# ESP32headerboard.net
KiCad netlist of a schematic drawn in Altium Designer
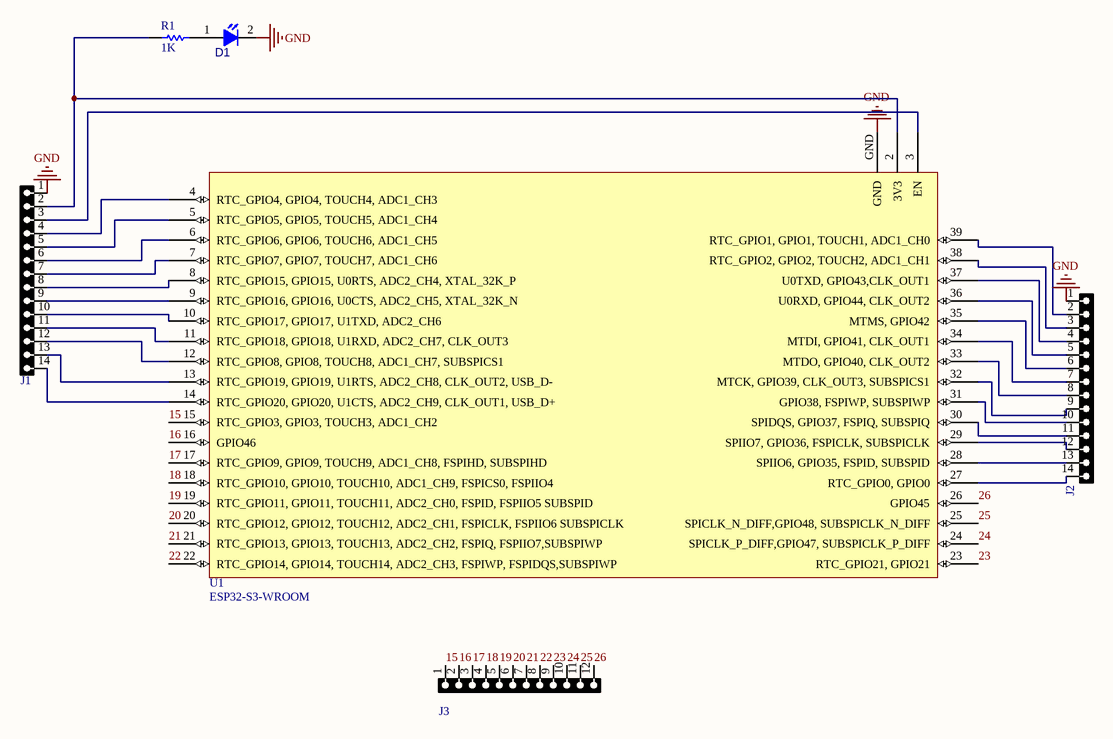
[diagram p0: ESP32headerboard.SchDoc]

(export (version "E")
  (design (tool "Eeschema 10.0.6"))
  (components
    (comp (ref "D1")
      (value "LED SMD 1206")
      (footprint "LED SMD 1206 (Blue)")
      (fields (field (name "DESIGNED BY:") "MJKhodami"))
      (libsource (lib "Devices_OMIDF") (part "LED SMD 1206"))
    )
    (comp (ref "J1")
      (value "HDRF14")
      (footprint "HDR 1X14")
      (description "CONN, HEADER, Female, pitch: 2.54mm, 14POS")
      (fields (field (name "DESIGNED BY:") "MJKhodami"))
      (libsource (lib "Devices_OMIDF") (part "HDR_1X14"))
    )
    (comp (ref "J2")
      (value "HDRF14")
      (footprint "HDR 1X14")
      (description "CONN, HEADER, Female, pitch: 2.54mm, 14POS")
      (fields (field (name "DESIGNED BY:") "MJKhodami"))
      (libsource (lib "Devices_OMIDF") (part "HDR_1X14"))
    )
    (comp (ref "J3")
      (value "HDRF12")
      (footprint "HDR 1X12")
      (description "CONN, HEADER, Female, pitch: 2.54mm, 12POS")
      (fields (field (name "DESIGNED BY:") "MJKhodami"))
      (libsource (lib "Devices_OMIDF") (part "HDR_1X12"))
    )
    (comp (ref "R1")
      (value "1K")
      (footprint "SMD-1206-RES")
      (description "Resistor SMD 1206")
      (fields (field (name "DESIGNED BY:") "MJKhodami"))
      (libsource (lib "Devices_OMIDF") (part "Resistor SMD 1206"))
    )
    (comp (ref "U1")
      (value "ESP32-S3-WROOM")
      (footprint "ESP32-S3-WROOM-1U-N8R8")
      (fields (field (name "DESIGNED BY:") "MJKhodami"))
      (libsource (lib "Devices_OMIDF") (part "ESP32-S3-WROOM-1U-N8R8"))
    )
  )
  (nets
    (net (code "1") (name "/15") (class "Default")
      (node (ref "J3") (pin "1") (pinfunction "1_1") (pintype "passive"))
      (node (ref "U1") (pin "15") (pinfunction "RTC_GPIO3,_GPIO3,_TOUCH3,_ADC1_CH2_15") (pintype "bidirectional"))
    )
    (net (code "2") (name "/16") (class "Default")
      (node (ref "J3") (pin "2") (pinfunction "2_2") (pintype "passive"))
      (node (ref "U1") (pin "16") (pinfunction "GPIO46_16") (pintype "bidirectional"))
    )
    (net (code "3") (name "/17") (class "Default")
      (node (ref "J3") (pin "3") (pinfunction "3_3") (pintype "passive"))
      (node (ref "U1") (pin "17") (pinfunction "RTC_GPIO9,_GPIO9,_TOUCH9,_ADC1_CH8,_FSPIHD,_SUBSPIHD_17") (pintype "bidirectional"))
    )
    (net (code "4") (name "/18") (class "Default")
      (node (ref "J3") (pin "4") (pinfunction "4_4") (pintype "passive"))
      (node (ref "U1") (pin "18") (pinfunction "RTC_GPIO10,_GPIO10,_TOUCH10,_ADC1_CH9,_FSPICS0,_FSPIIO4_18") (pintype "bidirectional"))
    )
    (net (code "5") (name "/19") (class "Default")
      (node (ref "J3") (pin "5") (pinfunction "5_5") (pintype "passive"))
      (node (ref "U1") (pin "19") (pinfunction "RTC_GPIO11,_GPIO11,_TOUCH11,_ADC2_CH0,_FSPID,_FSPIIO5_SUBSPID_19") (pintype "bidirectional"))
    )
    (net (code "6") (name "/20") (class "Default")
      (node (ref "J3") (pin "6") (pinfunction "6_6") (pintype "passive"))
      (node (ref "U1") (pin "20") (pinfunction "RTC_GPIO12,_GPIO12,_TOUCH12,_ADC2_CH1,_FSPICLK,_FSPIIO6_SUBSPICLK_20") (pintype "bidirectional"))
    )
    (net (code "7") (name "/21") (class "Default")
      (node (ref "J3") (pin "7") (pinfunction "7_7") (pintype "passive"))
      (node (ref "U1") (pin "21") (pinfunction "RTC_GPIO13,_GPIO13,_TOUCH13,_ADC2_CH2,_FSPIQ,_FSPIIO7,SUBSPIWP_21") (pintype "bidirectional"))
    )
    (net (code "8") (name "/22") (class "Default")
      (node (ref "J3") (pin "8") (pinfunction "8_8") (pintype "passive"))
      (node (ref "U1") (pin "22") (pinfunction "RTC_GPIO14,_GPIO14,_TOUCH14,_ADC2_CH3,_FSPIWP,_FSPIDQS,SUBSPIWP_22") (pintype "bidirectional"))
    )
    (net (code "9") (name "/23") (class "Default")
      (node (ref "J3") (pin "9") (pinfunction "9_9") (pintype "passive"))
      (node (ref "U1") (pin "23") (pinfunction "RTC_GPIO21,_GPIO21_23") (pintype "bidirectional"))
    )
    (net (code "10") (name "/24") (class "Default")
      (node (ref "J3") (pin "10") (pinfunction "10_10") (pintype "passive"))
      (node (ref "U1") (pin "24") (pinfunction "SPICLK_P_DIFF,GPIO47,_SUBSPICLK_P_DIFF_24") (pintype "bidirectional"))
    )
    (net (code "11") (name "/25") (class "Default")
      (node (ref "J3") (pin "11") (pinfunction "11_11") (pintype "passive"))
      (node (ref "U1") (pin "25") (pinfunction "SPICLK_N_DIFF,GPIO48,_SUBSPICLK_N_DIFF_25") (pintype "bidirectional"))
    )
    (net (code "12") (name "/26") (class "Default")
      (node (ref "J3") (pin "12") (pinfunction "12_12") (pintype "passive"))
      (node (ref "U1") (pin "26") (pinfunction "GPIO45_26") (pintype "bidirectional"))
    )
    (net (code "13") (name "GND") (class "Default")
      (node (ref "D1") (pin "2") (pinfunction "CATHODE_2") (pintype "passive"))
      (node (ref "J1") (pin "1") (pinfunction "1_1") (pintype "passive"))
      (node (ref "J2") (pin "1") (pinfunction "1_1") (pintype "passive"))
      (node (ref "U1") (pin "GND") (pinfunction "GND_GND") (pintype "passive"))
    )
    (net (code "14") (name "Net-(D1-ANODE)") (class "Default")
      (node (ref "D1") (pin "1") (pinfunction "ANODE_1") (pintype "passive"))
      (node (ref "R1") (pin "2") (pinfunction "2_2") (pintype "passive"))
    )
    (net (code "15") (name "Net-(U1-3V3)") (class "Default")
      (node (ref "J1") (pin "2") (pinfunction "2_2") (pintype "passive"))
      (node (ref "R1") (pin "1") (pinfunction "1_1") (pintype "passive"))
      (node (ref "U1") (pin "2") (pinfunction "3V3_2") (pintype "power_in"))
    )
    (net (code "16") (name "Net-(U1-EN)") (class "Default")
      (node (ref "J1") (pin "3") (pinfunction "3_3") (pintype "passive"))
      (node (ref "U1") (pin "3") (pinfunction "EN_3") (pintype "power_in"))
    )
    (net (code "17") (name "Net-(U1-GPIO38,_FSPIWP,_SUBSPIWP)") (class "Default")
      (node (ref "J2") (pin "10") (pinfunction "10_10") (pintype "passive"))
      (node (ref "U1") (pin "31") (pinfunction "GPIO38,_FSPIWP,_SUBSPIWP_31") (pintype "bidirectional"))
    )
    (net (code "18") (name "Net-(U1-MTCK,_GPIO39,_CLK_OUT3,_SUBSPICS1)") (class "Default")
      (node (ref "J2") (pin "9") (pinfunction "9_9") (pintype "passive"))
      (node (ref "U1") (pin "32") (pinfunction "MTCK,_GPIO39,_CLK_OUT3,_SUBSPICS1_32") (pintype "bidirectional"))
    )
    (net (code "19") (name "Net-(U1-MTDI,_GPIO41,_CLK_OUT1)") (class "Default")
      (node (ref "J2") (pin "7") (pinfunction "7_7") (pintype "passive"))
      (node (ref "U1") (pin "34") (pinfunction "MTDI,_GPIO41,_CLK_OUT1_34") (pintype "bidirectional"))
    )
    (net (code "20") (name "Net-(U1-MTDO,_GPIO40,_CLK_OUT2)") (class "Default")
      (node (ref "J2") (pin "8") (pinfunction "8_8") (pintype "passive"))
      (node (ref "U1") (pin "33") (pinfunction "MTDO,_GPIO40,_CLK_OUT2_33") (pintype "bidirectional"))
    )
    (net (code "21") (name "Net-(U1-MTMS,_GPIO42)") (class "Default")
      (node (ref "J2") (pin "6") (pinfunction "6_6") (pintype "passive"))
      (node (ref "U1") (pin "35") (pinfunction "MTMS,_GPIO42_35") (pintype "bidirectional"))
    )
    (net (code "22") (name "Net-(U1-RTC_GPIO0,_GPIO0)") (class "Default")
      (node (ref "J2") (pin "14") (pinfunction "14_14") (pintype "passive"))
      (node (ref "U1") (pin "27") (pinfunction "RTC_GPIO0,_GPIO0_27") (pintype "bidirectional"))
    )
    (net (code "23") (name "Net-(U1-RTC_GPIO1,_GPIO1,_TOUCH1,_ADC1_CH0)") (class "Default")
      (node (ref "J2") (pin "2") (pinfunction "2_2") (pintype "passive"))
      (node (ref "U1") (pin "39") (pinfunction "RTC_GPIO1,_GPIO1,_TOUCH1,_ADC1_CH0_39") (pintype "bidirectional"))
    )
    (net (code "24") (name "Net-(U1-RTC_GPIO2,_GPIO2,_TOUCH2,_ADC1_CH1)") (class "Default")
      (node (ref "J2") (pin "3") (pinfunction "3_3") (pintype "passive"))
      (node (ref "U1") (pin "38") (pinfunction "RTC_GPIO2,_GPIO2,_TOUCH2,_ADC1_CH1_38") (pintype "bidirectional"))
    )
    (net (code "25") (name "Net-(U1-RTC_GPIO4,_GPIO4,_TOUCH4,_ADC1_CH3)") (class "Default")
      (node (ref "J1") (pin "4") (pinfunction "4_4") (pintype "passive"))
      (node (ref "U1") (pin "4") (pinfunction "RTC_GPIO4,_GPIO4,_TOUCH4,_ADC1_CH3_4") (pintype "bidirectional"))
    )
    (net (code "26") (name "Net-(U1-RTC_GPIO5,_GPIO5,_TOUCH5,_ADC1_CH4)") (class "Default")
      (node (ref "J1") (pin "5") (pinfunction "5_5") (pintype "passive"))
      (node (ref "U1") (pin "5") (pinfunction "RTC_GPIO5,_GPIO5,_TOUCH5,_ADC1_CH4_5") (pintype "bidirectional"))
    )
    (net (code "27") (name "Net-(U1-RTC_GPIO6,_GPIO6,_TOUCH6,_ADC1_CH5)") (class "Default")
      (node (ref "J1") (pin "6") (pinfunction "6_6") (pintype "passive"))
      (node (ref "U1") (pin "6") (pinfunction "RTC_GPIO6,_GPIO6,_TOUCH6,_ADC1_CH5_6") (pintype "bidirectional"))
    )
    (net (code "28") (name "Net-(U1-RTC_GPIO7,_GPIO7,_TOUCH7,_ADC1_CH6)") (class "Default")
      (node (ref "J1") (pin "7") (pinfunction "7_7") (pintype "passive"))
      (node (ref "U1") (pin "7") (pinfunction "RTC_GPIO7,_GPIO7,_TOUCH7,_ADC1_CH6_7") (pintype "bidirectional"))
    )
    (net (code "29") (name "Net-(U1-RTC_GPIO8,_GPIO8,_TOUCH8,_ADC1_CH7,_SUBSPICS1)") (class "Default")
      (node (ref "J1") (pin "12") (pinfunction "12_12") (pintype "passive"))
      (node (ref "U1") (pin "12") (pinfunction "RTC_GPIO8,_GPIO8,_TOUCH8,_ADC1_CH7,_SUBSPICS1_12") (pintype "bidirectional"))
    )
    (net (code "30") (name "Net-(U1-RTC_GPIO15,_GPIO15,_U0RTS,_ADC2_CH4,_XTAL_32K_P)") (class "Default")
      (node (ref "J1") (pin "8") (pinfunction "8_8") (pintype "passive"))
      (node (ref "U1") (pin "8") (pinfunction "RTC_GPIO15,_GPIO15,_U0RTS,_ADC2_CH4,_XTAL_32K_P_8") (pintype "bidirectional"))
    )
    (net (code "31") (name "Net-(U1-RTC_GPIO16,_GPIO16,_U0CTS,_ADC2_CH5,_XTAL_32K_N)") (class "Default")
      (node (ref "J1") (pin "9") (pinfunction "9_9") (pintype "passive"))
      (node (ref "U1") (pin "9") (pinfunction "RTC_GPIO16,_GPIO16,_U0CTS,_ADC2_CH5,_XTAL_32K_N_9") (pintype "bidirectional"))
    )
    (net (code "32") (name "Net-(U1-RTC_GPIO17,_GPIO17,_U1TXD,_ADC2_CH6)") (class "Default")
      (node (ref "J1") (pin "10") (pinfunction "10_10") (pintype "passive"))
      (node (ref "U1") (pin "10") (pinfunction "RTC_GPIO17,_GPIO17,_U1TXD,_ADC2_CH6_10") (pintype "bidirectional"))
    )
    (net (code "33") (name "Net-(U1-RTC_GPIO18,_GPIO18,_U1RXD,_ADC2_CH7,_CLK_OUT3)") (class "Default")
      (node (ref "J1") (pin "11") (pinfunction "11_11") (pintype "passive"))
      (node (ref "U1") (pin "11") (pinfunction "RTC_GPIO18,_GPIO18,_U1RXD,_ADC2_CH7,_CLK_OUT3_11") (pintype "bidirectional"))
    )
    (net (code "34") (name "Net-(U1-RTC_GPIO19,_GPIO19,_U1RTS,_ADC2_CH8,_CLK_OUT2,_USB_D-)") (class "Default")
      (node (ref "J1") (pin "13") (pinfunction "13_13") (pintype "passive"))
      (node (ref "U1") (pin "13") (pinfunction "RTC_GPIO19,_GPIO19,_U1RTS,_ADC2_CH8,_CLK_OUT2,_USB_D-_13") (pintype "bidirectional"))
    )
    (net (code "35") (name "Net-(U1-RTC_GPIO20,_GPIO20,_U1CTS,_ADC2_CH9,_CLK_OUT1,_USB_D+)") (class "Default")
      (node (ref "J1") (pin "14") (pinfunction "14_14") (pintype "passive"))
      (node (ref "U1") (pin "14") (pinfunction "RTC_GPIO20,_GPIO20,_U1CTS,_ADC2_CH9,_CLK_OUT1,_USB_D+_14") (pintype "bidirectional"))
    )
    (net (code "36") (name "Net-(U1-SPIDQS,_GPIO37,_FSPIQ,_SUBSPIQ)") (class "Default")
      (node (ref "J2") (pin "11") (pinfunction "11_11") (pintype "passive"))
      (node (ref "U1") (pin "30") (pinfunction "SPIDQS,_GPIO37,_FSPIQ,_SUBSPIQ_30") (pintype "bidirectional"))
    )
    (net (code "37") (name "Net-(U1-SPIIO6,_GPIO35,_FSPID,_SUBSPID)") (class "Default")
      (node (ref "J2") (pin "13") (pinfunction "13_13") (pintype "passive"))
      (node (ref "U1") (pin "28") (pinfunction "SPIIO6,_GPIO35,_FSPID,_SUBSPID_28") (pintype "bidirectional"))
    )
    (net (code "38") (name "Net-(U1-SPIIO7,_GPIO36,_FSPICLK,_SUBSPICLK)") (class "Default")
      (node (ref "J2") (pin "12") (pinfunction "12_12") (pintype "passive"))
      (node (ref "U1") (pin "29") (pinfunction "SPIIO7,_GPIO36,_FSPICLK,_SUBSPICLK_29") (pintype "bidirectional"))
    )
    (net (code "39") (name "Net-(U1-U0RXD,_GPIO44,_CLK_OUT2)") (class "Default")
      (node (ref "J2") (pin "5") (pinfunction "5_5") (pintype "passive"))
      (node (ref "U1") (pin "36") (pinfunction "U0RXD,_GPIO44,_CLK_OUT2_36") (pintype "bidirectional"))
    )
    (net (code "40") (name "Net-(U1-U0TXD,_GPIO43,CLK_OUT1)") (class "Default")
      (node (ref "J2") (pin "4") (pinfunction "4_4") (pintype "passive"))
      (node (ref "U1") (pin "37") (pinfunction "U0TXD,_GPIO43,CLK_OUT1_37") (pintype "bidirectional"))
    )
  )
)
